# schm.net
KiCad netlist of a schematic drawn in EAGLE
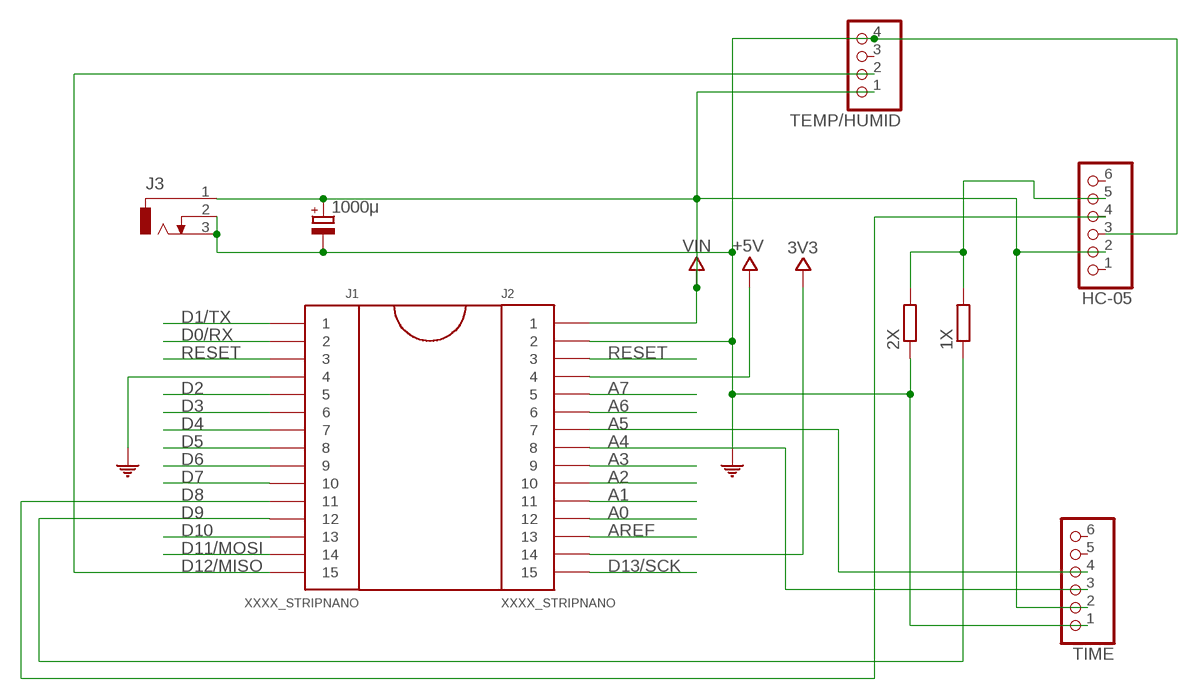
[diagram p0: schematic, sheet 1]

(export (version "E")
  (design (tool "Eeschema 10.0.6"))
  (components
    (comp (ref "1X")
      (value "R-EU_0207/10")
      (footprint "eagle-import:0207_10")
      (libsource (lib "eagle-import") (part "R-EU_0207/10"))
    )
    (comp (ref "2X")
      (value "R-EU_0207/10")
      (footprint "eagle-import:0207_10")
      (libsource (lib "eagle-import") (part "R-EU_0207/10"))
    )
    (comp (ref "1000μ")
      (value "CPOL-EUE3.5-10")
      (footprint "eagle-import:E3,5-10")
      (libsource (lib "eagle-import") (part "CPOL-EUE3.5-10"))
    )
    (comp (ref "HC-05")
      (value "PINHD-1X6/90")
      (footprint "eagle-import:1X06_90")
      (libsource (lib "eagle-import") (part "PINHD-1X6/90"))
    )
    (comp (ref "J1")
      (value "XXXX_STRIPNANO")
      (footprint "eagle-import:HEAD15-NOSS")
      (libsource (lib "eagle-import") (part "XXXX_STRIPNANO"))
    )
    (comp (ref "J2")
      (value "XXXX_STRIPNANO")
      (footprint "eagle-import:HEAD15-NOSS")
      (libsource (lib "eagle-import") (part "XXXX_STRIPNANO"))
    )
    (comp (ref "J3")
      (value "DCJ0303")
      (footprint "eagle-import:DCJ0303")
      (libsource (lib "eagle-import") (part "DCJ0303"))
    )
    (comp (ref "TEMP/HUMID")
      (value "PINHD-1X4")
      (footprint "eagle-import:1X04")
      (libsource (lib "eagle-import") (part "PINHD-1X4"))
    )
    (comp (ref "TIME")
      (value "PINHD-1X6/90")
      (footprint "eagle-import:1X06_90")
      (libsource (lib "eagle-import") (part "PINHD-1X6/90"))
    )
  )
  (nets
    (net (code "1") (name "+5V") (class "Default")
      (node (ref "J2") (pin "4") (pinfunction "4_4") (pintype "passive"))
    )
    (net (code "2") (name "/A0") (class "Default")
      (node (ref "J2") (pin "12") (pinfunction "12_12") (pintype "passive"))
    )
    (net (code "3") (name "/A1") (class "Default")
      (node (ref "J2") (pin "11") (pinfunction "11_11") (pintype "passive"))
    )
    (net (code "4") (name "/A2") (class "Default")
      (node (ref "J2") (pin "10") (pinfunction "10_10") (pintype "passive"))
    )
    (net (code "5") (name "/A3") (class "Default")
      (node (ref "J2") (pin "9") (pinfunction "9_9") (pintype "passive"))
    )
    (net (code "6") (name "/A4") (class "Default")
      (node (ref "J2") (pin "8") (pinfunction "8_8") (pintype "passive"))
      (node (ref "TIME") (pin "3") (pinfunction "3_3") (pintype "passive"))
    )
    (net (code "7") (name "/A5") (class "Default")
      (node (ref "J2") (pin "7") (pinfunction "7_7") (pintype "passive"))
      (node (ref "TIME") (pin "4") (pinfunction "4_4") (pintype "passive"))
    )
    (net (code "8") (name "/A6") (class "Default")
      (node (ref "J2") (pin "6") (pinfunction "6_6") (pintype "passive"))
    )
    (net (code "9") (name "/A7") (class "Default")
      (node (ref "J2") (pin "5") (pinfunction "5_5") (pintype "passive"))
    )
    (net (code "10") (name "/AREF") (class "Default")
      (node (ref "J2") (pin "13") (pinfunction "13_13") (pintype "passive"))
    )
    (net (code "11") (name "/D0{slash}RX") (class "Default")
      (node (ref "J1") (pin "2") (pinfunction "2_2") (pintype "passive"))
    )
    (net (code "12") (name "/D1{slash}TX") (class "Default")
      (node (ref "J1") (pin "1") (pinfunction "1_1") (pintype "passive"))
    )
    (net (code "13") (name "/D2") (class "Default")
      (node (ref "J1") (pin "5") (pinfunction "5_5") (pintype "passive"))
    )
    (net (code "14") (name "/D3") (class "Default")
      (node (ref "J1") (pin "6") (pinfunction "6_6") (pintype "passive"))
    )
    (net (code "15") (name "/D4") (class "Default")
      (node (ref "J1") (pin "7") (pinfunction "7_7") (pintype "passive"))
    )
    (net (code "16") (name "/D5") (class "Default")
      (node (ref "J1") (pin "8") (pinfunction "8_8") (pintype "passive"))
    )
    (net (code "17") (name "/D6") (class "Default")
      (node (ref "J1") (pin "9") (pinfunction "9_9") (pintype "passive"))
    )
    (net (code "18") (name "/D7") (class "Default")
      (node (ref "J1") (pin "10") (pinfunction "10_10") (pintype "passive"))
    )
    (net (code "19") (name "/D8") (class "Default")
      (node (ref "HC-05") (pin "4") (pinfunction "4_4") (pintype "passive"))
      (node (ref "J1") (pin "11") (pinfunction "11_11") (pintype "passive"))
    )
    (net (code "20") (name "/D9") (class "Default")
      (node (ref "1X") (pin "1") (pinfunction "1_1") (pintype "passive"))
      (node (ref "J1") (pin "12") (pinfunction "12_12") (pintype "passive"))
    )
    (net (code "21") (name "/D10") (class "Default")
      (node (ref "J1") (pin "13") (pinfunction "13_13") (pintype "passive"))
    )
    (net (code "22") (name "/D11{slash}MOSI") (class "Default")
      (node (ref "J1") (pin "14") (pinfunction "14_14") (pintype "passive"))
    )
    (net (code "23") (name "/D12{slash}MISO") (class "Default")
      (node (ref "J1") (pin "15") (pinfunction "15_15") (pintype "passive"))
      (node (ref "TEMP/HUMID") (pin "2") (pinfunction "2_2") (pintype "passive"))
    )
    (net (code "24") (name "/D13{slash}SCK") (class "Default")
      (node (ref "J2") (pin "15") (pinfunction "15_15") (pintype "passive"))
    )
    (net (code "25") (name "/RESET") (class "Default")
      (node (ref "J1") (pin "3") (pinfunction "3_3") (pintype "passive"))
      (node (ref "J2") (pin "3") (pinfunction "3_3") (pintype "passive"))
    )
    (net (code "26") (name "3V3") (class "Default")
      (node (ref "J2") (pin "14") (pinfunction "14_14") (pintype "passive"))
    )
    (net (code "27") (name "COM") (class "Default")
      (node (ref "1000μ") (pin "-") (pinfunction "-_-") (pintype "passive"))
      (node (ref "2X") (pin "1") (pinfunction "1_1") (pintype "passive"))
      (node (ref "HC-05") (pin "3") (pinfunction "3_3") (pintype "passive"))
      (node (ref "J1") (pin "4") (pinfunction "4_4") (pintype "passive"))
      (node (ref "J2") (pin "2") (pinfunction "2_2") (pintype "passive"))
      (node (ref "J3") (pin "2") (pinfunction "2_2") (pintype "passive"))
      (node (ref "J3") (pin "3") (pinfunction "3_3") (pintype "passive"))
      (node (ref "TEMP/HUMID") (pin "4") (pinfunction "4_4") (pintype "passive"))
      (node (ref "TIME") (pin "1") (pinfunction "1_1") (pintype "passive"))
    )
    (net (code "28") (name "Net-(1X-Pad2)") (class "Default")
      (node (ref "1X") (pin "2") (pinfunction "2_2") (pintype "passive"))
      (node (ref "2X") (pin "2") (pinfunction "2_2") (pintype "passive"))
      (node (ref "HC-05") (pin "5") (pinfunction "5_5") (pintype "passive"))
    )
    (net (code "29") (name "VIN") (class "Default")
      (node (ref "1000μ") (pin "+") (pinfunction "+_+") (pintype "passive"))
      (node (ref "HC-05") (pin "2") (pinfunction "2_2") (pintype "passive"))
      (node (ref "J2") (pin "1") (pinfunction "1_1") (pintype "passive"))
      (node (ref "J3") (pin "1") (pinfunction "1_1") (pintype "passive"))
      (node (ref "TEMP/HUMID") (pin "1") (pinfunction "1_1") (pintype "passive"))
      (node (ref "TIME") (pin "2") (pinfunction "2_2") (pintype "passive"))
    )
    (net (code "30") (name "unconnected-(HC-05-Pad1)") (class "Default")
      (node (ref "HC-05") (pin "1") (pinfunction "1_1") (pintype "passive"))
    )
    (net (code "31") (name "unconnected-(HC-05-Pad6)") (class "Default")
      (node (ref "HC-05") (pin "6") (pinfunction "6_6") (pintype "passive"))
    )
    (net (code "32") (name "unconnected-(TEMP/HUMID-Pad3)") (class "Default")
      (node (ref "TEMP/HUMID") (pin "3") (pinfunction "3_3") (pintype "passive"))
    )
    (net (code "33") (name "unconnected-(TIME-Pad5)") (class "Default")
      (node (ref "TIME") (pin "5") (pinfunction "5_5") (pintype "passive"))
    )
    (net (code "34") (name "unconnected-(TIME-Pad6)") (class "Default")
      (node (ref "TIME") (pin "6") (pinfunction "6_6") (pintype "passive"))
    )
  )
)
